# CH32V002J4M.net
KiCad netlist of a schematic drawn in Altium Designer
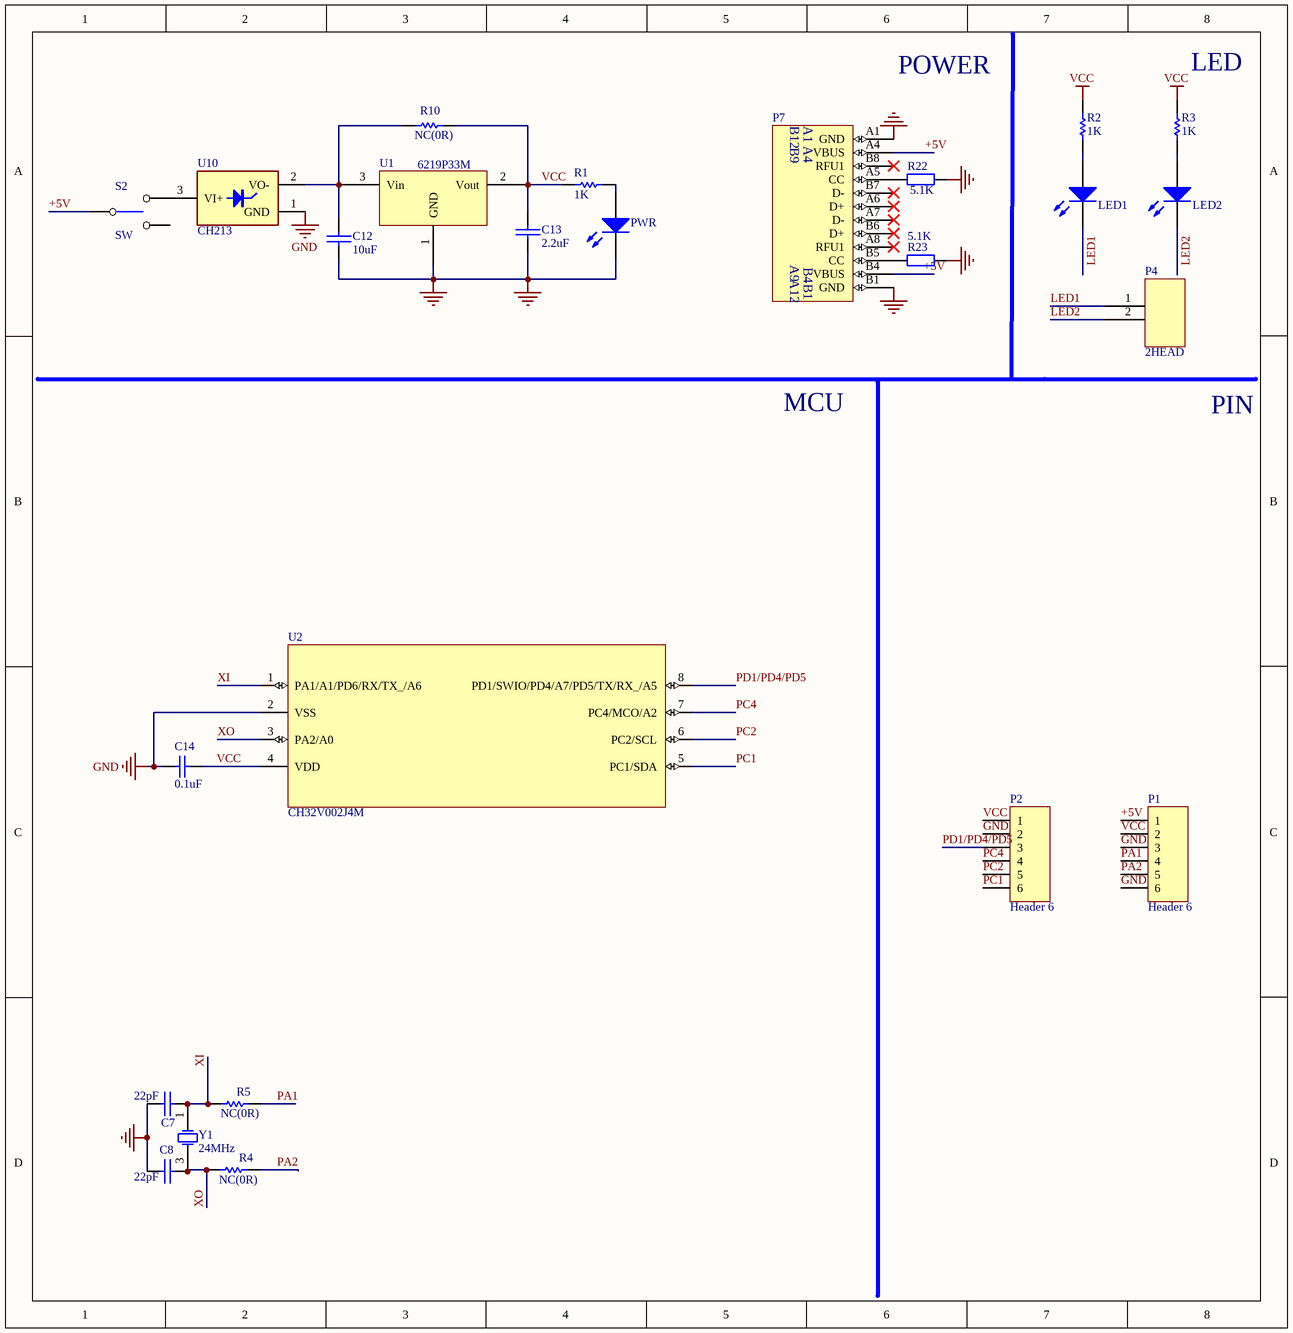
[diagram p0: CH32V002J4M.SchDoc]

(export (version "E")
  (design (tool "Eeschema 10.0.6"))
  (components
    (comp (ref "C7")
      (value "22pF")
      (footprint "0402_C")
      (description "Capacitor")
      (libsource (lib "*") (part "CAP"))
    )
    (comp (ref "C8")
      (value "22pF")
      (footprint "0402_C")
      (description "Capacitor")
      (libsource (lib "*") (part "CAP"))
    )
    (comp (ref "C12")
      (value "10uF")
      (footprint "0603_C")
      (description "Capacitor")
      (libsource (lib "wch_sch_others") (part "CAP"))
    )
    (comp (ref "C13")
      (value "2.2uF")
      (footprint "0402_C")
      (description "Capacitor")
      (libsource (lib "wch_sch_others") (part "CAP"))
    )
    (comp (ref "C14")
      (value "0.1uF")
      (footprint "0603_C")
      (description "Capacitor")
      (fields (field (name "PUBLISHER") "Altium Limited"))
      (libsource (lib "*") (part "Cap"))
    )
    (comp (ref "LED1")
      (value "LED1   blue")
      (footprint "0603+")
      (description "Typical INFRARED GaAs LED")
      (fields (field (name "PUBLISHER") "Altium Limited"))
      (libsource (lib "*") (part "LED0"))
    )
    (comp (ref "LED2")
      (value "LED2  blue")
      (footprint "0603+")
      (description "Typical INFRARED GaAs LED")
      (fields (field (name "PUBLISHER") "Altium Limited"))
      (libsource (lib "*") (part "LED0"))
    )
    (comp (ref "P1")
      (value "Header 6")
      (footprint "HDR1X6")
      (description "Header, 6-Pin")
      (fields (field (name "PUBLISHER") "Altium Limited"))
      (libsource (lib "Miscellaneous Connectors") (part "Header 6"))
    )
    (comp (ref "P2")
      (value "Header 6")
      (footprint "HDR1X6")
      (description "Header, 6-Pin")
      (fields (field (name "PUBLISHER") "Altium Limited"))
      (libsource (lib "Miscellaneous Connectors") (part "Header 6"))
    )
    (comp (ref "P4") (value "2HEAD") (footprint "SIP2-2.54mm") (libsource (lib "*") (part "2HEAD")))
    (comp (ref "P7")
      (value "TYPE-C")
      (footprint "TYPE-C-Receptacle-2.0")
      (libsource (lib "*") (part "TYPE-C1"))
    )
    (comp (ref "PWR")
      (value "POWER  red")
      (footprint "0603+")
      (description "Typical INFRARED GaAs LED")
      (fields (field (name "PUBLISHER") "Altium Limited"))
      (libsource (lib "") (part "LED0_1"))
    )
    (comp (ref "R1")
      (value "1K")
      (footprint "0402")
      (description "Semiconductor Resistor")
      (fields (field (name "PUBLISHER") "Altium Limited"))
      (libsource (lib "*") (part "Res Semi"))
    )
    (comp (ref "R2")
      (value "1K")
      (footprint "0402")
      (description "Semiconductor Resistor")
      (fields (field (name "PUBLISHER") "Altium Limited"))
      (libsource (lib "*") (part "Res Semi"))
    )
    (comp (ref "R3")
      (value "1K")
      (footprint "0402")
      (description "Semiconductor Resistor")
      (fields (field (name "PUBLISHER") "Altium Limited"))
      (libsource (lib "*") (part "Res Semi"))
    )
    (comp (ref "R4")
      (value "NC(0R)")
      (footprint "0402")
      (description "Semiconductor Resistor")
      (fields (field (name "Comment") "0R") (field (name "PUBLISHER") "Altium Limited"))
      (libsource (lib "*") (part "Res Semi"))
    )
    (comp (ref "R5")
      (value "NC(0R)")
      (footprint "0402")
      (description "Semiconductor Resistor")
      (fields (field (name "Comment") "0R") (field (name "PUBLISHER") "Altium Limited"))
      (libsource (lib "*") (part "Res Semi"))
    )
    (comp (ref "R10")
      (value "NC(0R)")
      (footprint "0402")
      (description "Semiconductor Resistor")
      (fields (field (name "Comment") "0R") (field (name "PUBLISHER") "Altium Limited"))
      (libsource (lib "*") (part "Res Semi"))
    )
    (comp (ref "R22")
      (value "5.1K")
      (footprint "0402")
      (description "Resistor")
      (libsource (lib "Miscellaneous Devices") (part "Res2"))
    )
    (comp (ref "R23")
      (value "5.1K")
      (footprint "0402")
      (description "Resistor")
      (libsource (lib "Miscellaneous Devices") (part "Res2"))
    )
    (comp (ref "S2") (value "SW") (footprint "SW1") (libsource (lib "*") (part "SW")))
    (comp (ref "U1")
      (value "6219P33M")
      (footprint "SOT-23")
      (libsource (lib "wch_sch_others") (part "6219P33M"))
    )
    (comp (ref "U2")
      (value "CH32V002J4M")
      (footprint "SOP8")
      (description "RISC-V MCU, 48MHz, ADC/UART/I2C")
      (libsource (lib "DHXXXSCH") (part "CH32V002J4M6"))
    )
    (comp (ref "U10")
      (value "CH213")
      (footprint "SOT-23-3")
      (description "Ideal Diode 5V*1A")
      (libsource (lib "CHXXX") (part "CH213E"))
    )
    (comp (ref "Y1")
      (value "24MHz")
      (footprint "XT3225")
      (description "Crystal Oscillator")
      (fields (field (name "PUBLISHER") "Altium Limited"))
      (libsource (lib "*") (part "XTAL"))
    )
  )
  (nets
    (net (code "1") (name "/+5V") (class "Default")
      (node (ref "P1") (pin "1") (pinfunction "1_1") (pintype "passive"))
      (node (ref "P7") (pin "A4") (pinfunction "VBUS_A4") (pintype "bidirectional"))
      (node (ref "P7") (pin "B4") (pinfunction "VBUS_B4") (pintype "bidirectional"))
      (node (ref "S2") (pin "1") (pinfunction "1_1") (pintype "passive"))
    )
    (net (code "2") (name "/LED1") (class "Default")
      (node (ref "LED1") (pin "2") (pinfunction "K_2") (pintype "passive"))
      (node (ref "P4") (pin "1") (pintype "passive"))
    )
    (net (code "3") (name "/LED2") (class "Default")
      (node (ref "LED2") (pin "2") (pinfunction "K_2") (pintype "passive"))
      (node (ref "P4") (pin "2") (pintype "passive"))
    )
    (net (code "4") (name "/PA1") (class "Default")
      (node (ref "P1") (pin "4") (pinfunction "4_4") (pintype "passive"))
      (node (ref "R5") (pin "2") (pinfunction "2_2") (pintype "passive"))
    )
    (net (code "5") (name "/PA2") (class "Default")
      (node (ref "P1") (pin "5") (pinfunction "5_5") (pintype "passive"))
      (node (ref "R4") (pin "2") (pinfunction "2_2") (pintype "passive"))
    )
    (net (code "6") (name "/PC1") (class "Default")
      (node (ref "P2") (pin "6") (pinfunction "6_6") (pintype "passive"))
      (node (ref "U2") (pin "5") (pinfunction "PC1/SDA_5") (pintype "bidirectional"))
    )
    (net (code "7") (name "/PC2") (class "Default")
      (node (ref "P2") (pin "5") (pinfunction "5_5") (pintype "passive"))
      (node (ref "U2") (pin "6") (pinfunction "PC2/SCL_6") (pintype "bidirectional"))
    )
    (net (code "8") (name "/PC4") (class "Default")
      (node (ref "P2") (pin "4") (pinfunction "4_4") (pintype "passive"))
      (node (ref "U2") (pin "7") (pinfunction "PC4/MCO/A2_7") (pintype "bidirectional"))
    )
    (net (code "9") (name "/PD1{slash}PD4{slash}PD5") (class "Default")
      (node (ref "P2") (pin "3") (pinfunction "3_3") (pintype "passive"))
      (node (ref "U2") (pin "8") (pinfunction "PD1/SWIO/PD4/A7/PD5/TX/RX_/A5_8") (pintype "bidirectional"))
    )
    (net (code "10") (name "/XI") (class "Default")
      (node (ref "C7") (pin "2") (pinfunction "2_2") (pintype "passive"))
      (node (ref "R5") (pin "1") (pinfunction "1_1") (pintype "passive"))
      (node (ref "U2") (pin "1") (pinfunction "PA1/A1/PD6/RX/TX_/A6_1") (pintype "bidirectional"))
      (node (ref "Y1") (pin "1") (pinfunction "OSC1_1") (pintype "passive"))
    )
    (net (code "11") (name "/XO") (class "Default")
      (node (ref "C8") (pin "2") (pinfunction "2_2") (pintype "passive"))
      (node (ref "R4") (pin "1") (pinfunction "1_1") (pintype "passive"))
      (node (ref "U2") (pin "3") (pinfunction "PA2/A0_3") (pintype "bidirectional"))
      (node (ref "Y1") (pin "3") (pinfunction "OSC2_3") (pintype "passive"))
    )
    (net (code "12") (name "GND") (class "Default")
      (node (ref "C12") (pin "2") (pinfunction "2_2") (pintype "passive"))
      (node (ref "C13") (pin "1") (pinfunction "1_1") (pintype "passive"))
      (node (ref "C14") (pin "2") (pinfunction "2_2") (pintype "passive"))
      (node (ref "C7") (pin "1") (pinfunction "1_1") (pintype "passive"))
      (node (ref "C8") (pin "1") (pinfunction "1_1") (pintype "passive"))
      (node (ref "P1") (pin "3") (pinfunction "3_3") (pintype "passive"))
      (node (ref "P1") (pin "6") (pinfunction "6_6") (pintype "passive"))
      (node (ref "P2") (pin "2") (pinfunction "2_2") (pintype "passive"))
      (node (ref "P7") (pin "A1") (pinfunction "GND_A1") (pintype "bidirectional"))
      (node (ref "P7") (pin "B1") (pinfunction "GND_B1") (pintype "bidirectional"))
      (node (ref "PWR") (pin "2") (pinfunction "K_2") (pintype "passive"))
      (node (ref "R22") (pin "2") (pinfunction "2_2") (pintype "passive"))
      (node (ref "R23") (pin "2") (pinfunction "2_2") (pintype "passive"))
      (node (ref "U1") (pin "1") (pinfunction "GND_1") (pintype "passive"))
      (node (ref "U10") (pin "1") (pinfunction "GND_1") (pintype "power_in"))
      (node (ref "U2") (pin "2") (pinfunction "VSS_2") (pintype "power_in"))
    )
    (net (code "13") (name "Net-(LED1-A)") (class "Default")
      (node (ref "LED1") (pin "1") (pinfunction "A_1") (pintype "passive"))
      (node (ref "R2") (pin "2") (pinfunction "2_2") (pintype "passive"))
    )
    (net (code "14") (name "Net-(LED2-A)") (class "Default")
      (node (ref "LED2") (pin "1") (pinfunction "A_1") (pintype "passive"))
      (node (ref "R3") (pin "2") (pinfunction "2_2") (pintype "passive"))
    )
    (net (code "15") (name "Net-(P7-CC-PadA5)") (class "Default")
      (node (ref "P7") (pin "A5") (pinfunction "CC_A5") (pintype "bidirectional"))
      (node (ref "R22") (pin "1") (pinfunction "1_1") (pintype "passive"))
    )
    (net (code "16") (name "Net-(P7-CC-PadB5)") (class "Default")
      (node (ref "P7") (pin "B5") (pinfunction "CC_B5") (pintype "bidirectional"))
      (node (ref "R23") (pin "1") (pinfunction "1_1") (pintype "passive"))
    )
    (net (code "17") (name "Net-(PWR-A)") (class "Default")
      (node (ref "PWR") (pin "1") (pinfunction "A_1") (pintype "passive"))
      (node (ref "R1") (pin "1") (pinfunction "1_1") (pintype "passive"))
    )
    (net (code "18") (name "Net-(U1-Vin)") (class "Default")
      (node (ref "C12") (pin "1") (pinfunction "1_1") (pintype "passive"))
      (node (ref "R10") (pin "1") (pinfunction "1_1") (pintype "passive"))
      (node (ref "U1") (pin "3") (pinfunction "Vin_3") (pintype "passive"))
      (node (ref "U10") (pin "2") (pinfunction "VO-_2") (pintype "power_in"))
    )
    (net (code "19") (name "Net-(U10-VI+)") (class "Default")
      (node (ref "S2") (pin "3") (pinfunction "3_3") (pintype "passive"))
      (node (ref "U10") (pin "3") (pinfunction "VI+_3") (pintype "power_in"))
    )
    (net (code "20") (name "VCC") (class "Default")
      (node (ref "C13") (pin "2") (pinfunction "2_2") (pintype "passive"))
      (node (ref "C14") (pin "1") (pinfunction "1_1") (pintype "passive"))
      (node (ref "P1") (pin "2") (pinfunction "2_2") (pintype "passive"))
      (node (ref "P2") (pin "1") (pinfunction "1_1") (pintype "passive"))
      (node (ref "R1") (pin "2") (pinfunction "2_2") (pintype "passive"))
      (node (ref "R10") (pin "2") (pinfunction "2_2") (pintype "passive"))
      (node (ref "R2") (pin "1") (pinfunction "1_1") (pintype "passive"))
      (node (ref "R3") (pin "1") (pinfunction "1_1") (pintype "passive"))
      (node (ref "U1") (pin "2") (pinfunction "Vout_2") (pintype "passive"))
      (node (ref "U2") (pin "4") (pinfunction "VDD_4") (pintype "power_in"))
    )
    (net (code "21") (name "unconnected-(P7-D+-PadA6)") (class "Default")
      (node (ref "P7") (pin "A6") (pinfunction "D+_A6") (pintype "bidirectional+no_connect"))
    )
    (net (code "22") (name "unconnected-(P7-D+-PadB6)") (class "Default")
      (node (ref "P7") (pin "B6") (pinfunction "D+_B6") (pintype "bidirectional+no_connect"))
    )
    (net (code "23") (name "unconnected-(P7-D--PadA7)") (class "Default")
      (node (ref "P7") (pin "A7") (pinfunction "D-_A7") (pintype "bidirectional+no_connect"))
    )
    (net (code "24") (name "unconnected-(P7-D--PadB7)") (class "Default")
      (node (ref "P7") (pin "B7") (pinfunction "D-_B7") (pintype "bidirectional+no_connect"))
    )
    (net (code "25") (name "unconnected-(P7-RFU1-PadA8)") (class "Default")
      (node (ref "P7") (pin "A8") (pinfunction "RFU1_A8") (pintype "bidirectional+no_connect"))
    )
    (net (code "26") (name "unconnected-(P7-RFU1-PadB8)") (class "Default")
      (node (ref "P7") (pin "B8") (pinfunction "RFU1_B8") (pintype "bidirectional+no_connect"))
    )
    (net (code "27") (name "unconnected-(S2-Pad2)") (class "Default")
      (node (ref "S2") (pin "2") (pinfunction "2_2") (pintype "passive"))
    )
  )
)
